# bblan95xx.net
KiCad netlist of a schematic drawn in EAGLE
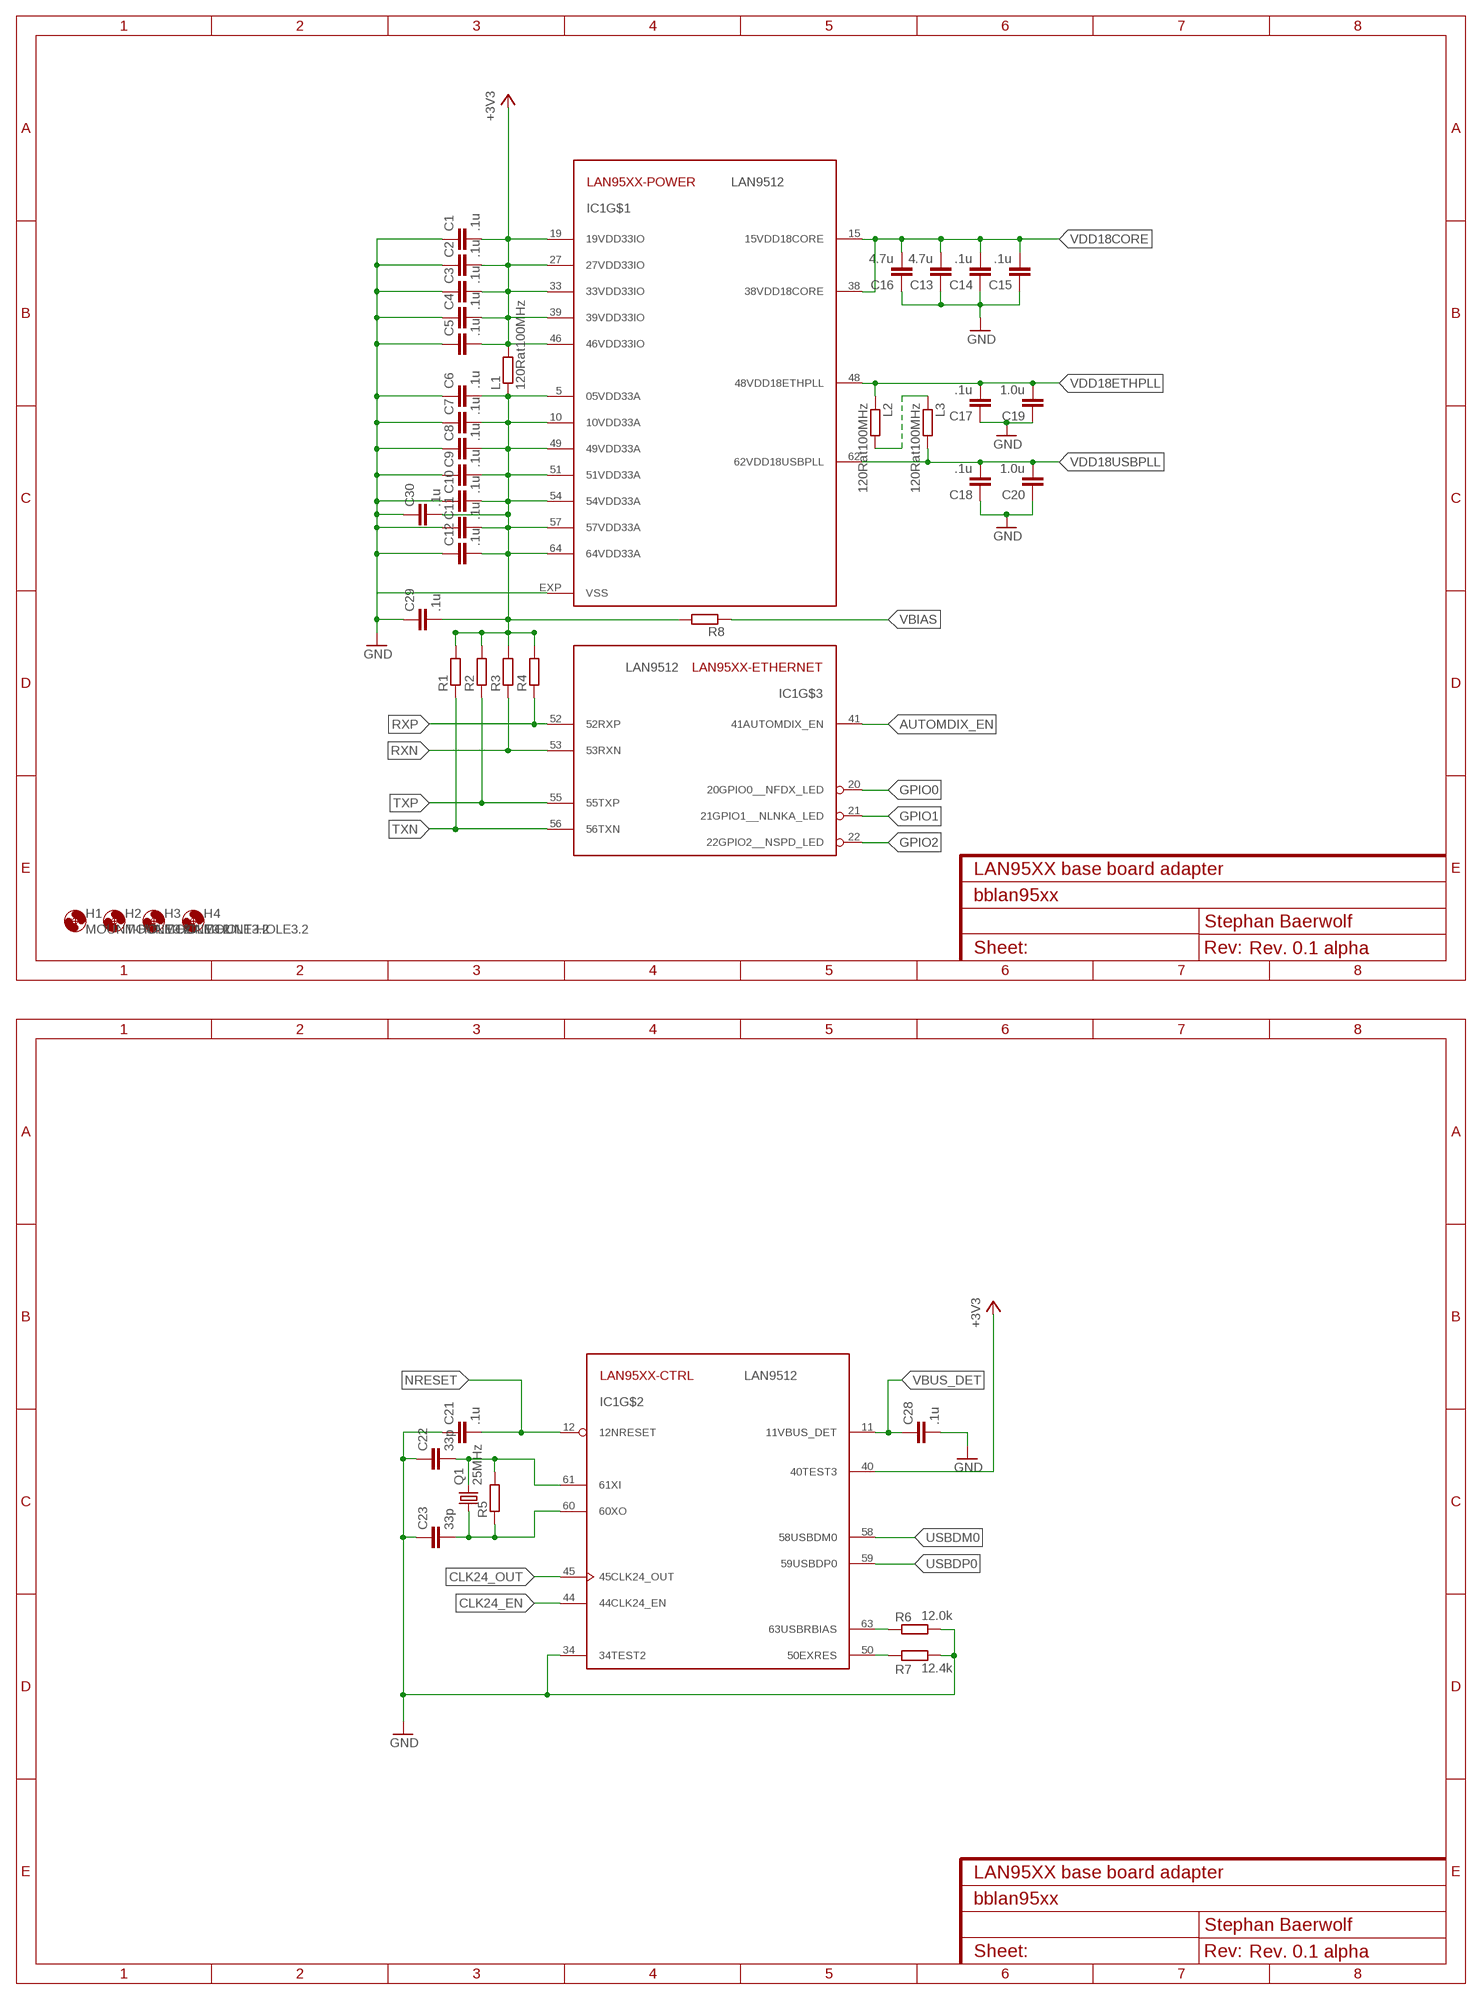
[diagram p0: schematic, sheet 1, part 1 of 2]
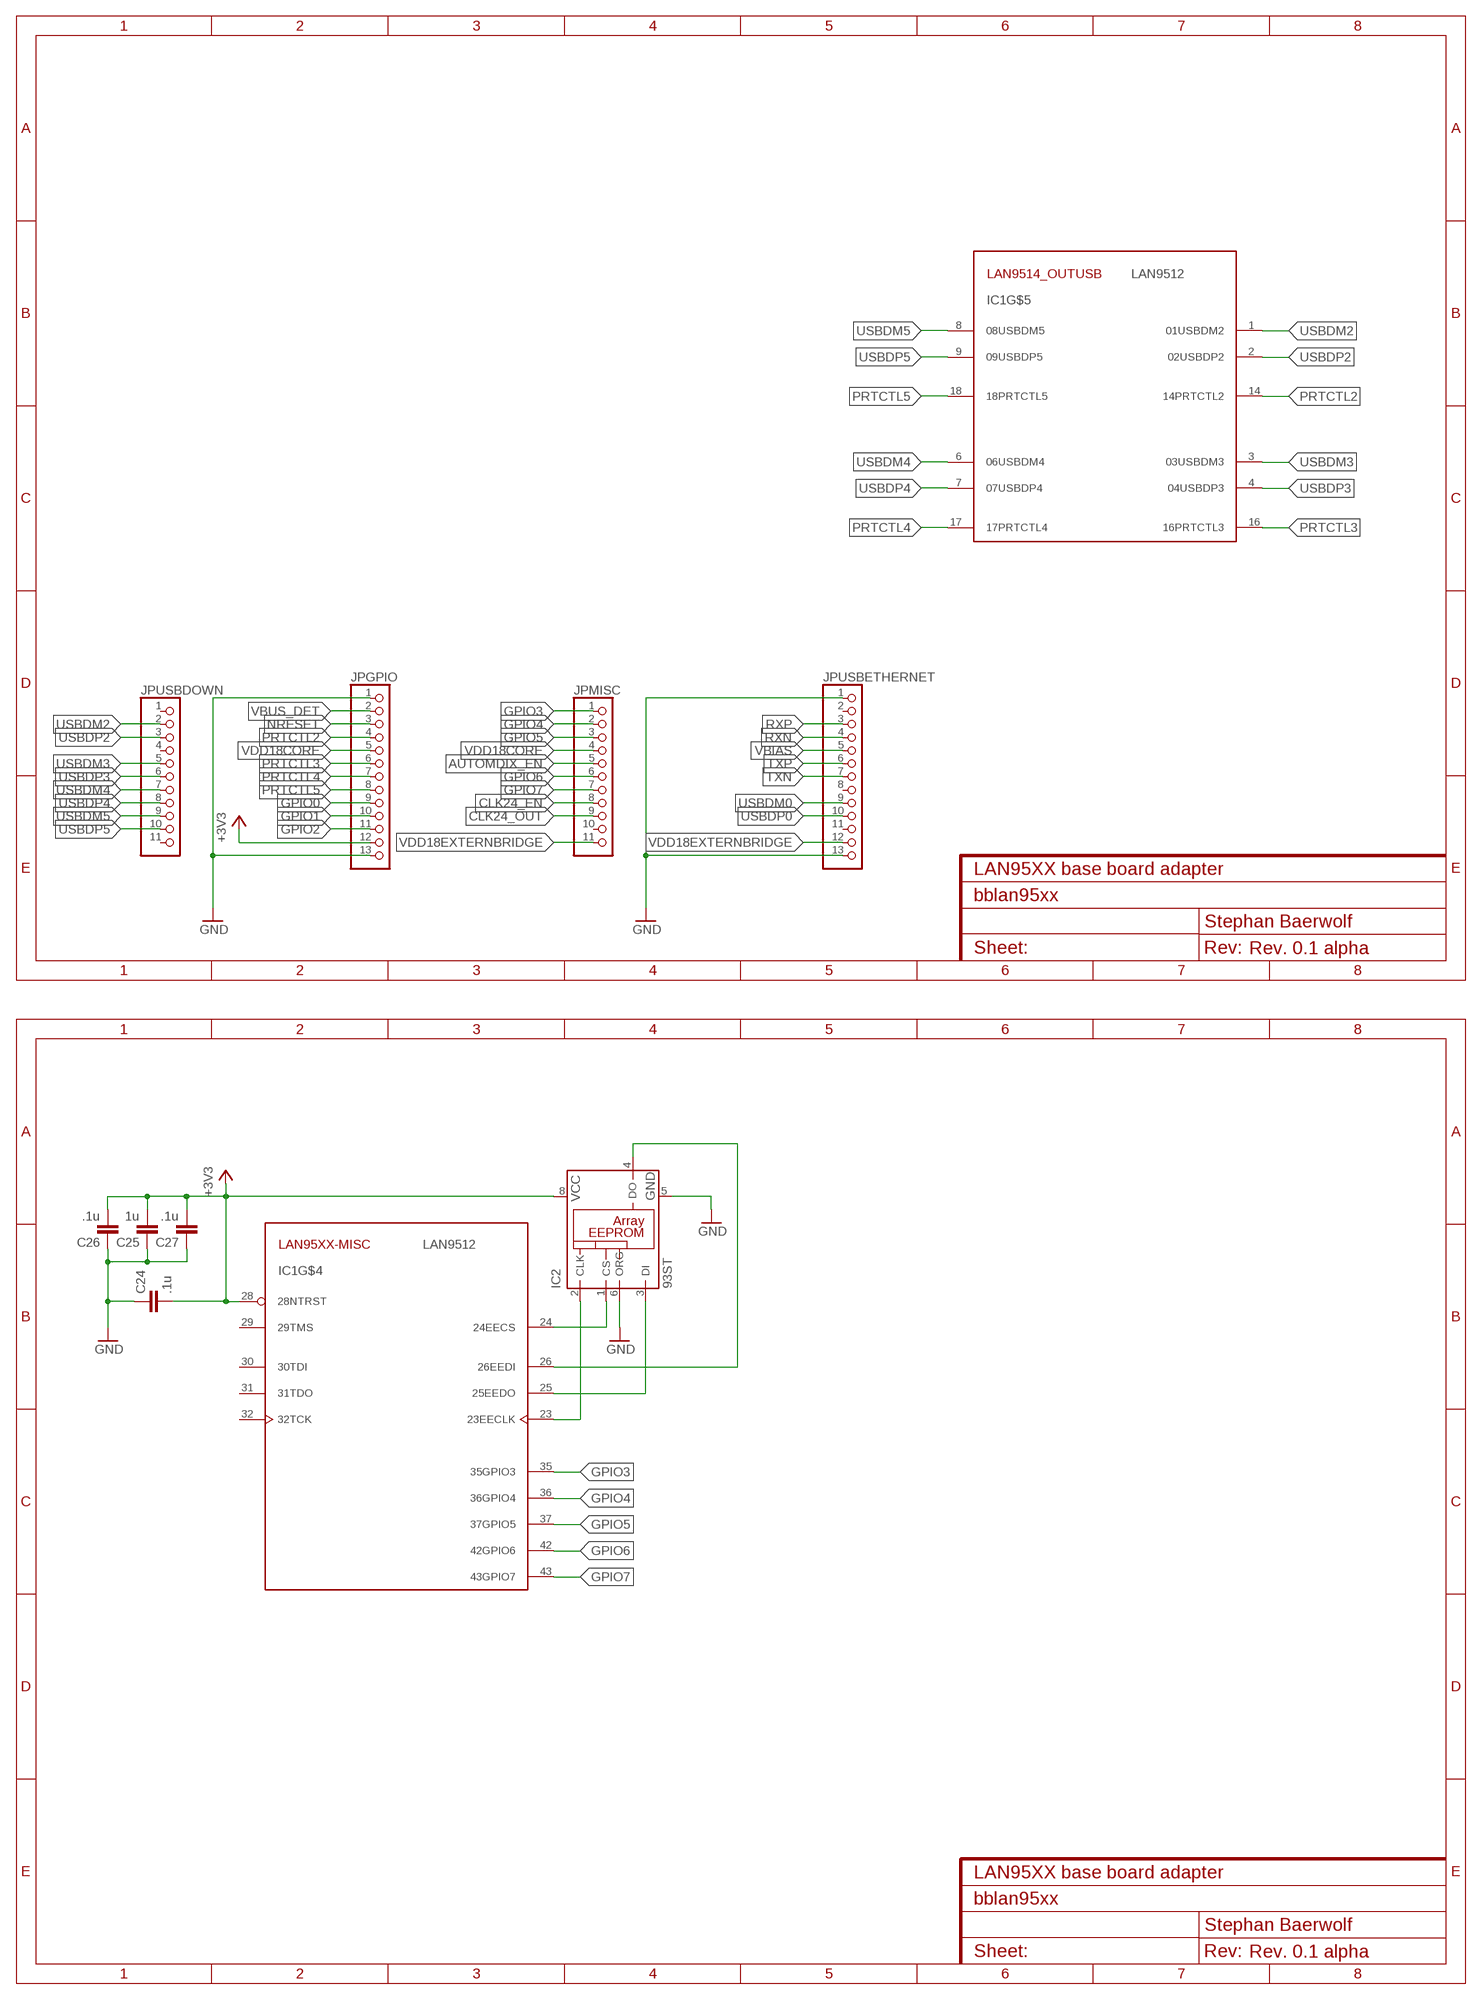
[diagram p1: schematic, sheet 1, part 2 of 2]

(export (version "E")
  (design (tool "Eeschema 10.0.6"))
  (components
    (comp (ref "C1")
      (value ".1u")
      (footprint "eagle-import:C0805K")
      (libsource (lib "eagle-import") (part "C-EUC0805K"))
    )
    (comp (ref "C2")
      (value ".1u")
      (footprint "eagle-import:C0805K")
      (libsource (lib "eagle-import") (part "C-EUC0805K"))
    )
    (comp (ref "C3")
      (value ".1u")
      (footprint "eagle-import:C0805K")
      (libsource (lib "eagle-import") (part "C-EUC0805K"))
    )
    (comp (ref "C4")
      (value ".1u")
      (footprint "eagle-import:C0805K")
      (libsource (lib "eagle-import") (part "C-EUC0805K"))
    )
    (comp (ref "C5")
      (value ".1u")
      (footprint "eagle-import:C0805K")
      (libsource (lib "eagle-import") (part "C-EUC0805K"))
    )
    (comp (ref "C6")
      (value ".1u")
      (footprint "eagle-import:C0805K")
      (libsource (lib "eagle-import") (part "C-EUC0805K"))
    )
    (comp (ref "C7")
      (value ".1u")
      (footprint "eagle-import:C0805K")
      (libsource (lib "eagle-import") (part "C-EUC0805K"))
    )
    (comp (ref "C8")
      (value ".1u")
      (footprint "eagle-import:C0805K")
      (libsource (lib "eagle-import") (part "C-EUC0805K"))
    )
    (comp (ref "C9")
      (value ".1u")
      (footprint "eagle-import:C0603K")
      (libsource (lib "eagle-import") (part "C-EUC0603K"))
    )
    (comp (ref "C10")
      (value ".1u")
      (footprint "eagle-import:C0603K")
      (libsource (lib "eagle-import") (part "C-EUC0603K"))
    )
    (comp (ref "C11")
      (value ".1u")
      (footprint "eagle-import:C0603K")
      (libsource (lib "eagle-import") (part "C-EUC0603K"))
    )
    (comp (ref "C12")
      (value ".1u")
      (footprint "eagle-import:C0805K")
      (libsource (lib "eagle-import") (part "C-EUC0805K"))
    )
    (comp (ref "C13")
      (value "4.7u")
      (footprint "eagle-import:C0805K")
      (libsource (lib "eagle-import") (part "C-EUC0805K"))
    )
    (comp (ref "C14")
      (value ".1u")
      (footprint "eagle-import:C0603K")
      (libsource (lib "eagle-import") (part "C-EUC0603K"))
    )
    (comp (ref "C15")
      (value ".1u")
      (footprint "eagle-import:C0603K")
      (libsource (lib "eagle-import") (part "C-EUC0603K"))
    )
    (comp (ref "C16")
      (value "4.7u")
      (footprint "eagle-import:C0805K")
      (libsource (lib "eagle-import") (part "C-EUC0805K"))
    )
    (comp (ref "C17")
      (value ".1u")
      (footprint "eagle-import:C0603K")
      (libsource (lib "eagle-import") (part "C-EUC0603K"))
    )
    (comp (ref "C18")
      (value ".1u")
      (footprint "eagle-import:C0603K")
      (libsource (lib "eagle-import") (part "C-EUC0603K"))
    )
    (comp (ref "C19")
      (value "1.0u")
      (footprint "eagle-import:C0805K")
      (libsource (lib "eagle-import") (part "C-EUC0805K"))
    )
    (comp (ref "C20")
      (value "1.0u")
      (footprint "eagle-import:C0805K")
      (libsource (lib "eagle-import") (part "C-EUC0805K"))
    )
    (comp (ref "C21")
      (value ".1u")
      (footprint "eagle-import:C0603K")
      (libsource (lib "eagle-import") (part "C-EUC0603K"))
    )
    (comp (ref "C22")
      (value "33p")
      (footprint "eagle-import:C0603K")
      (libsource (lib "eagle-import") (part "C-EUC0603K"))
    )
    (comp (ref "C23")
      (value "33p")
      (footprint "eagle-import:C0603K")
      (libsource (lib "eagle-import") (part "C-EUC0603K"))
    )
    (comp (ref "C24")
      (value ".1u")
      (footprint "eagle-import:C0603K")
      (libsource (lib "eagle-import") (part "C-EUC0603K"))
    )
    (comp (ref "C25")
      (value "1u")
      (footprint "eagle-import:C0805K")
      (libsource (lib "eagle-import") (part "C-EUC0805K"))
    )
    (comp (ref "C26")
      (value ".1u")
      (footprint "eagle-import:C0805K")
      (libsource (lib "eagle-import") (part "C-EUC0805K"))
    )
    (comp (ref "C27")
      (value ".1u")
      (footprint "eagle-import:C0805K")
      (libsource (lib "eagle-import") (part "C-EUC0805K"))
    )
    (comp (ref "C28")
      (value ".1u")
      (footprint "eagle-import:C0603K")
      (libsource (lib "eagle-import") (part "C-EUC0603K"))
    )
    (comp (ref "C29")
      (value ".1u")
      (footprint "eagle-import:C0603K")
      (libsource (lib "eagle-import") (part "C-EUC0603K"))
    )
    (comp (ref "C30")
      (value ".1u")
      (footprint "eagle-import:C0603K")
      (libsource (lib "eagle-import") (part "C-EUC0603K"))
    )
    (comp (ref "H1")
      (value "MOUNT-HOLE3.2")
      (footprint "eagle-import:3,2")
      (libsource (lib "eagle-import") (part "MOUNT-HOLE3.2"))
    )
    (comp (ref "H2")
      (value "MOUNT-HOLE3.2")
      (footprint "eagle-import:3,2")
      (libsource (lib "eagle-import") (part "MOUNT-HOLE3.2"))
    )
    (comp (ref "H3")
      (value "MOUNT-HOLE3.2")
      (footprint "eagle-import:3,2")
      (libsource (lib "eagle-import") (part "MOUNT-HOLE3.2"))
    )
    (comp (ref "H4")
      (value "MOUNT-HOLE3.2")
      (footprint "eagle-import:3,2")
      (libsource (lib "eagle-import") (part "MOUNT-HOLE3.2"))
    )
    (comp (ref "IC1")
      (value "LAN9512")
      (footprint "eagle-import:QFN64-9X9-EXTRALONG")
      (libsource (lib "eagle-import") (part "LAN95XX"))
    )
    (comp (ref "IC2")
      (value "93ST")
      (footprint "eagle-import:SO-08")
      (fields (field (name "MF") "MICROCHIP") (field (name "MPN") "93LC66/SN"))
      (libsource (lib "eagle-import") (part "93SNLC66"))
    )
    (comp (ref "JPGPIO")
      (value "PINHD-1X13")
      (footprint "eagle-import:1X13")
      (libsource (lib "eagle-import") (part "PINHD-1X13"))
    )
    (comp (ref "JPMISC")
      (value "PINHD-1X11")
      (footprint "eagle-import:1X11")
      (libsource (lib "eagle-import") (part "PINHD-1X11"))
    )
    (comp (ref "JPUSBDOWN")
      (value "PINHD-1X11")
      (footprint "eagle-import:1X11")
      (libsource (lib "eagle-import") (part "PINHD-1X11"))
    )
    (comp (ref "JPUSBETHERNET")
      (value "PINHD-1X13")
      (footprint "eagle-import:1X13")
      (libsource (lib "eagle-import") (part "PINHD-1X13"))
    )
    (comp (ref "L1")
      (value "120Rat100MHz")
      (footprint "eagle-import:R0805")
      (libsource (lib "eagle-import") (part "R-EU_R0805"))
    )
    (comp (ref "L2")
      (value "120Rat100MHz")
      (footprint "eagle-import:R0805")
      (libsource (lib "eagle-import") (part "R-EU_R0805"))
    )
    (comp (ref "L3")
      (value "120Rat100MHz")
      (footprint "eagle-import:R0805")
      (libsource (lib "eagle-import") (part "R-EU_R0805"))
    )
    (comp (ref "Q1")
      (value "25MHz")
      (footprint "eagle-import:CRYSTAL-SMD-5X3")
      (libsource (lib "eagle-import") (part "CRYSTAL5X3"))
    )
    (comp (ref "R1")
      (value "R-EU_R0603")
      (footprint "eagle-import:R0603")
      (libsource (lib "eagle-import") (part "R-EU_R0603"))
    )
    (comp (ref "R2")
      (value "R-EU_R0603")
      (footprint "eagle-import:R0603")
      (libsource (lib "eagle-import") (part "R-EU_R0603"))
    )
    (comp (ref "R3")
      (value "R-EU_R0603")
      (footprint "eagle-import:R0603")
      (libsource (lib "eagle-import") (part "R-EU_R0603"))
    )
    (comp (ref "R4")
      (value "R-EU_R0603")
      (footprint "eagle-import:R0603")
      (libsource (lib "eagle-import") (part "R-EU_R0603"))
    )
    (comp (ref "R5")
      (value "R-EU_R0603")
      (footprint "eagle-import:R0603")
      (libsource (lib "eagle-import") (part "R-EU_R0603"))
    )
    (comp (ref "R6")
      (value "12.0k")
      (footprint "eagle-import:R0603")
      (libsource (lib "eagle-import") (part "R-EU_R0603"))
    )
    (comp (ref "R7")
      (value "12.4k")
      (footprint "eagle-import:R0603")
      (libsource (lib "eagle-import") (part "R-EU_R0603"))
    )
    (comp (ref "R8")
      (value "R-EU_R0402")
      (footprint "eagle-import:R0402")
      (libsource (lib "eagle-import") (part "R-EU_R0402"))
    )
  )
  (nets
    (net (code "1") (name "+3V3") (class "Default")
      (node (ref "C1") (pin "2") (pinfunction "2_2") (pintype "passive"))
      (node (ref "C2") (pin "2") (pinfunction "2_2") (pintype "passive"))
      (node (ref "C24") (pin "2") (pinfunction "2_2") (pintype "passive"))
      (node (ref "C25") (pin "2") (pinfunction "2_2") (pintype "passive"))
      (node (ref "C26") (pin "2") (pinfunction "2_2") (pintype "passive"))
      (node (ref "C27") (pin "2") (pinfunction "2_2") (pintype "passive"))
      (node (ref "C3") (pin "2") (pinfunction "2_2") (pintype "passive"))
      (node (ref "C4") (pin "2") (pinfunction "2_2") (pintype "passive"))
      (node (ref "C5") (pin "2") (pinfunction "2_2") (pintype "passive"))
      (node (ref "IC1") (pin "19") (pinfunction "19VDD33IO_19") (pintype "power_in"))
      (node (ref "IC1") (pin "27") (pinfunction "27VDD33IO_27") (pintype "power_in"))
      (node (ref "IC1") (pin "28") (pinfunction "28NTRST_28") (pintype "input"))
      (node (ref "IC1") (pin "33") (pinfunction "33VDD33IO_33") (pintype "power_in"))
      (node (ref "IC1") (pin "39") (pinfunction "39VDD33IO_39") (pintype "power_in"))
      (node (ref "IC1") (pin "40") (pinfunction "40TEST3_40") (pintype "passive"))
      (node (ref "IC1") (pin "46") (pinfunction "46VDD33IO_46") (pintype "power_in"))
      (node (ref "IC2") (pin "8") (pinfunction "VCC_8") (pintype "power_in"))
      (node (ref "JPGPIO") (pin "12") (pinfunction "12_12") (pintype "passive"))
      (node (ref "L1") (pin "2") (pinfunction "2_2") (pintype "passive"))
    )
    (net (code "2") (name "AUTOMDIX_EN") (class "Default")
      (node (ref "IC1") (pin "41") (pinfunction "41AUTOMDIX_EN_41") (pintype "input"))
      (node (ref "JPMISC") (pin "5") (pinfunction "5_5") (pintype "passive"))
    )
    (net (code "3") (name "CLK24_EN") (class "Default")
      (node (ref "IC1") (pin "44") (pinfunction "44CLK24_EN_44") (pintype "input"))
      (node (ref "JPMISC") (pin "8") (pinfunction "8_8") (pintype "passive"))
    )
    (net (code "4") (name "CLK24_OUT") (class "Default")
      (node (ref "IC1") (pin "45") (pinfunction "45CLK24_OUT_45") (pintype "output"))
      (node (ref "JPMISC") (pin "9") (pinfunction "9_9") (pintype "passive"))
    )
    (net (code "5") (name "GND") (class "Default")
      (node (ref "C1") (pin "1") (pinfunction "1_1") (pintype "passive"))
      (node (ref "C10") (pin "1") (pinfunction "1_1") (pintype "passive"))
      (node (ref "C11") (pin "1") (pinfunction "1_1") (pintype "passive"))
      (node (ref "C12") (pin "1") (pinfunction "1_1") (pintype "passive"))
      (node (ref "C13") (pin "1") (pinfunction "1_1") (pintype "passive"))
      (node (ref "C14") (pin "1") (pinfunction "1_1") (pintype "passive"))
      (node (ref "C15") (pin "1") (pinfunction "1_1") (pintype "passive"))
      (node (ref "C16") (pin "1") (pinfunction "1_1") (pintype "passive"))
      (node (ref "C17") (pin "1") (pinfunction "1_1") (pintype "passive"))
      (node (ref "C18") (pin "1") (pinfunction "1_1") (pintype "passive"))
      (node (ref "C19") (pin "1") (pinfunction "1_1") (pintype "passive"))
      (node (ref "C2") (pin "1") (pinfunction "1_1") (pintype "passive"))
      (node (ref "C20") (pin "1") (pinfunction "1_1") (pintype "passive"))
      (node (ref "C21") (pin "1") (pinfunction "1_1") (pintype "passive"))
      (node (ref "C22") (pin "1") (pinfunction "1_1") (pintype "passive"))
      (node (ref "C23") (pin "1") (pinfunction "1_1") (pintype "passive"))
      (node (ref "C24") (pin "1") (pinfunction "1_1") (pintype "passive"))
      (node (ref "C25") (pin "1") (pinfunction "1_1") (pintype "passive"))
      (node (ref "C26") (pin "1") (pinfunction "1_1") (pintype "passive"))
      (node (ref "C27") (pin "1") (pinfunction "1_1") (pintype "passive"))
      (node (ref "C28") (pin "2") (pinfunction "2_2") (pintype "passive"))
      (node (ref "C29") (pin "1") (pinfunction "1_1") (pintype "passive"))
      (node (ref "C3") (pin "1") (pinfunction "1_1") (pintype "passive"))
      (node (ref "C30") (pin "1") (pinfunction "1_1") (pintype "passive"))
      (node (ref "C4") (pin "1") (pinfunction "1_1") (pintype "passive"))
      (node (ref "C5") (pin "1") (pinfunction "1_1") (pintype "passive"))
      (node (ref "C6") (pin "1") (pinfunction "1_1") (pintype "passive"))
      (node (ref "C7") (pin "1") (pinfunction "1_1") (pintype "passive"))
      (node (ref "C8") (pin "1") (pinfunction "1_1") (pintype "passive"))
      (node (ref "C9") (pin "1") (pinfunction "1_1") (pintype "passive"))
      (node (ref "IC1") (pin "34") (pinfunction "34TEST2_34") (pintype "passive"))
      (node (ref "IC1") (pin "EXP") (pinfunction "VSS_EXP") (pintype "power_in"))
      (node (ref "IC2") (pin "5") (pinfunction "GND_5") (pintype "power_in"))
      (node (ref "IC2") (pin "6") (pinfunction "ORG_6") (pintype "input"))
      (node (ref "JPGPIO") (pin "1") (pinfunction "1_1") (pintype "passive"))
      (node (ref "JPGPIO") (pin "13") (pinfunction "13_13") (pintype "passive"))
      (node (ref "JPUSBETHERNET") (pin "1") (pinfunction "1_1") (pintype "passive"))
      (node (ref "JPUSBETHERNET") (pin "13") (pinfunction "13_13") (pintype "passive"))
      (node (ref "R6") (pin "2") (pinfunction "2_2") (pintype "passive"))
      (node (ref "R7") (pin "2") (pinfunction "2_2") (pintype "passive"))
    )
    (net (code "6") (name "GPIO0") (class "Default")
      (node (ref "IC1") (pin "20") (pinfunction "20GPIO0__NFDX_LED_20") (pintype "bidirectional"))
      (node (ref "JPGPIO") (pin "9") (pinfunction "9_9") (pintype "passive"))
    )
    (net (code "7") (name "GPIO1") (class "Default")
      (node (ref "IC1") (pin "21") (pinfunction "21GPIO1__NLNKA_LED_21") (pintype "bidirectional"))
      (node (ref "JPGPIO") (pin "10") (pinfunction "10_10") (pintype "passive"))
    )
    (net (code "8") (name "GPIO2") (class "Default")
      (node (ref "IC1") (pin "22") (pinfunction "22GPIO2__NSPD_LED_22") (pintype "bidirectional"))
      (node (ref "JPGPIO") (pin "11") (pinfunction "11_11") (pintype "passive"))
    )
    (net (code "9") (name "GPIO3") (class "Default")
      (node (ref "IC1") (pin "35") (pinfunction "35GPIO3_35") (pintype "bidirectional"))
      (node (ref "JPMISC") (pin "1") (pinfunction "1_1") (pintype "passive"))
    )
    (net (code "10") (name "GPIO4") (class "Default")
      (node (ref "IC1") (pin "36") (pinfunction "36GPIO4_36") (pintype "bidirectional"))
      (node (ref "JPMISC") (pin "2") (pinfunction "2_2") (pintype "passive"))
    )
    (net (code "11") (name "GPIO5") (class "Default")
      (node (ref "IC1") (pin "37") (pinfunction "37GPIO5_37") (pintype "bidirectional"))
      (node (ref "JPMISC") (pin "3") (pinfunction "3_3") (pintype "passive"))
    )
    (net (code "12") (name "GPIO6") (class "Default")
      (node (ref "IC1") (pin "42") (pinfunction "42GPIO6_42") (pintype "bidirectional"))
      (node (ref "JPMISC") (pin "6") (pinfunction "6_6") (pintype "passive"))
    )
    (net (code "13") (name "GPIO7") (class "Default")
      (node (ref "IC1") (pin "43") (pinfunction "43GPIO7_43") (pintype "bidirectional"))
      (node (ref "JPMISC") (pin "7") (pinfunction "7_7") (pintype "passive"))
    )
    (net (code "14") (name "NRESET") (class "Default")
      (node (ref "C21") (pin "2") (pinfunction "2_2") (pintype "passive"))
      (node (ref "IC1") (pin "12") (pinfunction "12NRESET_12") (pintype "input"))
      (node (ref "JPGPIO") (pin "3") (pinfunction "3_3") (pintype "passive"))
    )
    (net (code "15") (name "Net-(IC1A-05VDD33A)") (class "Default")
      (node (ref "C10") (pin "2") (pinfunction "2_2") (pintype "passive"))
      (node (ref "C11") (pin "2") (pinfunction "2_2") (pintype "passive"))
      (node (ref "C12") (pin "2") (pinfunction "2_2") (pintype "passive"))
      (node (ref "C29") (pin "2") (pinfunction "2_2") (pintype "passive"))
      (node (ref "C30") (pin "2") (pinfunction "2_2") (pintype "passive"))
      (node (ref "C6") (pin "2") (pinfunction "2_2") (pintype "passive"))
      (node (ref "C7") (pin "2") (pinfunction "2_2") (pintype "passive"))
      (node (ref "C8") (pin "2") (pinfunction "2_2") (pintype "passive"))
      (node (ref "C9") (pin "2") (pinfunction "2_2") (pintype "passive"))
      (node (ref "IC1") (pin "10") (pinfunction "10VDD33A_10") (pintype "power_in"))
      (node (ref "IC1") (pin "49") (pinfunction "49VDD33A_49") (pintype "power_in"))
      (node (ref "IC1") (pin "5") (pinfunction "05VDD33A_5") (pintype "power_in"))
      (node (ref "IC1") (pin "51") (pinfunction "51VDD33A_51") (pintype "power_in"))
      (node (ref "IC1") (pin "54") (pinfunction "54VDD33A_54") (pintype "power_in"))
      (node (ref "IC1") (pin "57") (pinfunction "57VDD33A_57") (pintype "power_in"))
      (node (ref "IC1") (pin "64") (pinfunction "64VDD33A_64") (pintype "power_in"))
      (node (ref "L1") (pin "1") (pinfunction "1_1") (pintype "passive"))
      (node (ref "R1") (pin "2") (pinfunction "2_2") (pintype "passive"))
      (node (ref "R2") (pin "2") (pinfunction "2_2") (pintype "passive"))
      (node (ref "R3") (pin "2") (pinfunction "2_2") (pintype "passive"))
      (node (ref "R4") (pin "2") (pinfunction "2_2") (pintype "passive"))
      (node (ref "R8") (pin "2") (pinfunction "2_2") (pintype "passive"))
    )
    (net (code "16") (name "Net-(IC1B-50EXRES)") (class "Default")
      (node (ref "IC1") (pin "50") (pinfunction "50EXRES_50") (pintype "passive"))
      (node (ref "R7") (pin "1") (pinfunction "1_1") (pintype "passive"))
    )
    (net (code "17") (name "Net-(IC1B-60XO)") (class "Default")
      (node (ref "C23") (pin "2") (pinfunction "2_2") (pintype "passive"))
      (node (ref "IC1") (pin "60") (pinfunction "60XO_60") (pintype "input"))
      (node (ref "Q1") (pin "1") (pinfunction "1_1") (pintype "passive"))
      (node (ref "R5") (pin "1") (pinfunction "1_1") (pintype "passive"))
    )
    (net (code "18") (name "Net-(IC1B-61XI)") (class "Default")
      (node (ref "C22") (pin "2") (pinfunction "2_2") (pintype "passive"))
      (node (ref "IC1") (pin "61") (pinfunction "61XI_61") (pintype "input"))
      (node (ref "Q1") (pin "3") (pinfunction "2_3") (pintype "passive"))
      (node (ref "R5") (pin "2") (pinfunction "2_2") (pintype "passive"))
    )
    (net (code "19") (name "Net-(IC1B-63USBRBIAS)") (class "Default")
      (node (ref "IC1") (pin "63") (pinfunction "63USBRBIAS_63") (pintype "passive"))
      (node (ref "R6") (pin "1") (pinfunction "1_1") (pintype "passive"))
    )
    (net (code "20") (name "Net-(IC1D-23EECLK)") (class "Default")
      (node (ref "IC1") (pin "23") (pinfunction "23EECLK_23") (pintype "output"))
      (node (ref "IC2") (pin "2") (pinfunction "CLK_2") (pintype "input"))
    )
    (net (code "21") (name "Net-(IC1D-24EECS)") (class "Default")
      (node (ref "IC1") (pin "24") (pinfunction "24EECS_24") (pintype "output"))
      (node (ref "IC2") (pin "1") (pinfunction "CS_1") (pintype "input"))
    )
    (net (code "22") (name "Net-(IC1D-25EEDO)") (class "Default")
      (node (ref "IC1") (pin "25") (pinfunction "25EEDO_25") (pintype "output"))
      (node (ref "IC2") (pin "3") (pinfunction "DI_3") (pintype "input"))
    )
    (net (code "23") (name "Net-(IC1D-26EEDI)") (class "Default")
      (node (ref "IC1") (pin "26") (pinfunction "26EEDI_26") (pintype "input"))
      (node (ref "IC2") (pin "4") (pinfunction "DO_4") (pintype "tri_state"))
    )
    (net (code "24") (name "PRTCTL2") (class "Default")
      (node (ref "IC1") (pin "14") (pinfunction "14PRTCTL2_14") (pintype "bidirectional"))
      (node (ref "JPGPIO") (pin "4") (pinfunction "4_4") (pintype "passive"))
    )
    (net (code "25") (name "PRTCTL3") (class "Default")
      (node (ref "IC1") (pin "16") (pinfunction "16PRTCTL3_16") (pintype "bidirectional"))
      (node (ref "JPGPIO") (pin "6") (pinfunction "6_6") (pintype "passive"))
    )
    (net (code "26") (name "PRTCTL4") (class "Default")
      (node (ref "IC1") (pin "17") (pinfunction "17PRTCTL4_17") (pintype "bidirectional"))
      (node (ref "JPGPIO") (pin "7") (pinfunction "7_7") (pintype "passive"))
    )
    (net (code "27") (name "PRTCTL5") (class "Default")
      (node (ref "IC1") (pin "18") (pinfunction "18PRTCTL5_18") (pintype "bidirectional"))
      (node (ref "JPGPIO") (pin "8") (pinfunction "8_8") (pintype "passive"))
    )
    (net (code "28") (name "RXN") (class "Default")
      (node (ref "IC1") (pin "53") (pinfunction "53RXN_53") (pintype "bidirectional"))
      (node (ref "JPUSBETHERNET") (pin "4") (pinfunction "4_4") (pintype "passive"))
      (node (ref "R3") (pin "1") (pinfunction "1_1") (pintype "passive"))
    )
    (net (code "29") (name "RXP") (class "Default")
      (node (ref "IC1") (pin "52") (pinfunction "52RXP_52") (pintype "bidirectional"))
      (node (ref "JPUSBETHERNET") (pin "3") (pinfunction "3_3") (pintype "passive"))
      (node (ref "R4") (pin "1") (pinfunction "1_1") (pintype "passive"))
    )
    (net (code "30") (name "TXN") (class "Default")
      (node (ref "IC1") (pin "56") (pinfunction "56TXN_56") (pintype "bidirectional"))
      (node (ref "JPUSBETHERNET") (pin "7") (pinfunction "7_7") (pintype "passive"))
      (node (ref "R1") (pin "1") (pinfunction "1_1") (pintype "passive"))
    )
    (net (code "31") (name "TXP") (class "Default")
      (node (ref "IC1") (pin "55") (pinfunction "55TXP_55") (pintype "bidirectional"))
      (node (ref "JPUSBETHERNET") (pin "6") (pinfunction "6_6") (pintype "passive"))
      (node (ref "R2") (pin "1") (pinfunction "1_1") (pintype "passive"))
    )
    (net (code "32") (name "USBDM0") (class "Default")
      (node (ref "IC1") (pin "58") (pinfunction "58USBDM0_58") (pintype "bidirectional"))
      (node (ref "JPUSBETHERNET") (pin "9") (pinfunction "9_9") (pintype "passive"))
    )
    (net (code "33") (name "USBDM2") (class "Default")
      (node (ref "IC1") (pin "1") (pinfunction "01USBDM2_1") (pintype "bidirectional"))
      (node (ref "JPUSBDOWN") (pin "2") (pinfunction "2_2") (pintype "passive"))
    )
    (net (code "34") (name "USBDM3") (class "Default")
      (node (ref "IC1") (pin "3") (pinfunction "03USBDM3_3") (pintype "bidirectional"))
      (node (ref "JPUSBDOWN") (pin "5") (pinfunction "5_5") (pintype "passive"))
    )
    (net (code "35") (name "USBDM4") (class "Default")
      (node (ref "IC1") (pin "6") (pinfunction "06USBDM4_6") (pintype "bidirectional"))
      (node (ref "JPUSBDOWN") (pin "7") (pinfunction "7_7") (pintype "passive"))
    )
    (net (code "36") (name "USBDM5") (class "Default")
      (node (ref "IC1") (pin "8") (pinfunction "08USBDM5_8") (pintype "bidirectional"))
      (node (ref "JPUSBDOWN") (pin "9") (pinfunction "9_9") (pintype "passive"))
    )
    (net (code "37") (name "USBDP0") (class "Default")
      (node (ref "IC1") (pin "59") (pinfunction "59USBDP0_59") (pintype "bidirectional"))
      (node (ref "JPUSBETHERNET") (pin "10") (pinfunction "10_10") (pintype "passive"))
    )
    (net (code "38") (name "USBDP2") (class "Default")
      (node (ref "IC1") (pin "2") (pinfunction "02USBDP2_2") (pintype "bidirectional"))
      (node (ref "JPUSBDOWN") (pin "3") (pinfunction "3_3") (pintype "passive"))
    )
    (net (code "39") (name "USBDP3") (class "Default")
      (node (ref "IC1") (pin "4") (pinfunction "04USBDP3_4") (pintype "bidirectional"))
      (node (ref "JPUSBDOWN") (pin "6") (pinfunction "6_6") (pintype "passive"))
    )
    (net (code "40") (name "USBDP4") (class "Default")
      (node (ref "IC1") (pin "7") (pinfunction "07USBDP4_7") (pintype "bidirectional"))
      (node (ref "JPUSBDOWN") (pin "8") (pinfunction "8_8") (pintype "passive"))
    )
    (net (code "41") (name "USBDP5") (class "Default")
      (node (ref "IC1") (pin "9") (pinfunction "09USBDP5_9") (pintype "bidirectional"))
      (node (ref "JPUSBDOWN") (pin "10") (pinfunction "10_10") (pintype "passive"))
    )
    (net (code "42") (name "VBIAS") (class "Default")
      (node (ref "JPUSBETHERNET") (pin "5") (pinfunction "5_5") (pintype "passive"))
      (node (ref "R8") (pin "1") (pinfunction "1_1") (pintype "passive"))
    )
    (net (code "43") (name "VBUS_DET") (class "Default")
      (node (ref "C28") (pin "1") (pinfunction "1_1") (pintype "passive"))
      (node (ref "IC1") (pin "11") (pinfunction "11VBUS_DET_11") (pintype "passive"))
      (node (ref "JPGPIO") (pin "2") (pinfunction "2_2") (pintype "passive"))
    )
    (net (code "44") (name "VDD18CORE") (class "Default")
      (node (ref "C13") (pin "2") (pinfunction "2_2") (pintype "passive"))
      (node (ref "C14") (pin "2") (pinfunction "2_2") (pintype "passive"))
      (node (ref "C15") (pin "2") (pinfunction "2_2") (pintype "passive"))
      (node (ref "C16") (pin "2") (pinfunction "2_2") (pintype "passive"))
      (node (ref "IC1") (pin "15") (pinfunction "15VDD18CORE_15") (pintype "power_in"))
      (node (ref "IC1") (pin "38") (pinfunction "38VDD18CORE_38") (pintype "power_in"))
      (node (ref "JPGPIO") (pin "5") (pinfunction "5_5") (pintype "passive"))
      (node (ref "JPMISC") (pin "4") (pinfunction "4_4") (pintype "passive"))
    )
    (net (code "45") (name "VDD18ETHPLL") (class "Default")
      (node (ref "C17") (pin "2") (pinfunction "2_2") (pintype "passive"))
      (node (ref "C19") (pin "2") (pinfunction "2_2") (pintype "passive"))
      (node (ref "IC1") (pin "48") (pinfunction "48VDD18ETHPLL_48") (pintype "power_in"))
      (node (ref "L2") (pin "1") (pinfunction "1_1") (pintype "passive"))
    )
    (net (code "46") (name "VDD18EXTERNBRIDGE") (class "Default")
      (node (ref "JPMISC") (pin "11") (pinfunction "11_11") (pintype "passive"))
      (node (ref "JPUSBETHERNET") (pin "12") (pinfunction "12_12") (pintype "passive"))
      (node (ref "L2") (pin "2") (pinfunction "2_2") (pintype "passive"))
      (node (ref "L3") (pin "1") (pinfunction "1_1") (pintype "passive"))
    )
    (net (code "47") (name "VDD18USBPLL") (class "Default")
      (node (ref "C18") (pin "2") (pinfunction "2_2") (pintype "passive"))
      (node (ref "C20") (pin "2") (pinfunction "2_2") (pintype "passive"))
      (node (ref "IC1") (pin "62") (pinfunction "62VDD18USBPLL_62") (pintype "power_in"))
      (node (ref "L3") (pin "2") (pinfunction "2_2") (pintype "passive"))
    )
    (net (code "48") (name "unconnected-(IC1D-29TMS-Pad29)") (class "Default")
      (node (ref "IC1") (pin "29") (pinfunction "29TMS_29") (pintype "input"))
    )
    (net (code "49") (name "unconnected-(IC1D-30TDI-Pad30)") (class "Default")
      (node (ref "IC1") (pin "30") (pinfunction "30TDI_30") (pintype "input"))
    )
    (net (code "50") (name "unconnected-(IC1D-31TDO-Pad31)") (class "Default")
      (node (ref "IC1") (pin "31") (pinfunction "31TDO_31") (pintype "output"))
    )
    (net (code "51") (name "unconnected-(IC1D-32TCK-Pad32)") (class "Default")
      (node (ref "IC1") (pin "32") (pinfunction "32TCK_32") (pintype "input"))
    )
    (net (code "52") (name "unconnected-(IC2-NU-Pad7)") (class "Default")
      (node (ref "IC2") (pin "7") (pinfunction "NU_7") (pintype "passive"))
    )
    (net (code "53") (name "unconnected-(JPMISC-Pad10)") (class "Default")
      (node (ref "JPMISC") (pin "10") (pinfunction "10_10") (pintype "passive"))
    )
    (net (code "54") (name "unconnected-(JPUSBDOWN-Pad1)") (class "Default")
      (node (ref "JPUSBDOWN") (pin "1") (pinfunction "1_1") (pintype "passive"))
    )
    (net (code "55") (name "unconnected-(JPUSBDOWN-Pad4)") (class "Default")
      (node (ref "JPUSBDOWN") (pin "4") (pinfunction "4_4") (pintype "passive"))
    )
    (net (code "56") (name "unconnected-(JPUSBDOWN-Pad11)") (class "Default")
      (node (ref "JPUSBDOWN") (pin "11") (pinfunction "11_11") (pintype "passive"))
    )
    (net (code "57") (name "unconnected-(JPUSBETHERNET-Pad2)") (class "Default")
      (node (ref "JPUSBETHERNET") (pin "2") (pinfunction "2_2") (pintype "passive"))
    )
    (net (code "58") (name "unconnected-(JPUSBETHERNET-Pad8)") (class "Default")
      (node (ref "JPUSBETHERNET") (pin "8") (pinfunction "8_8") (pintype "passive"))
    )
    (net (code "59") (name "unconnected-(JPUSBETHERNET-Pad11)") (class "Default")
      (node (ref "JPUSBETHERNET") (pin "11") (pinfunction "11_11") (pintype "passive"))
    )
  )
)
